# EAA690_RFID_Door.net
KiCad netlist of a schematic drawn in EAGLE
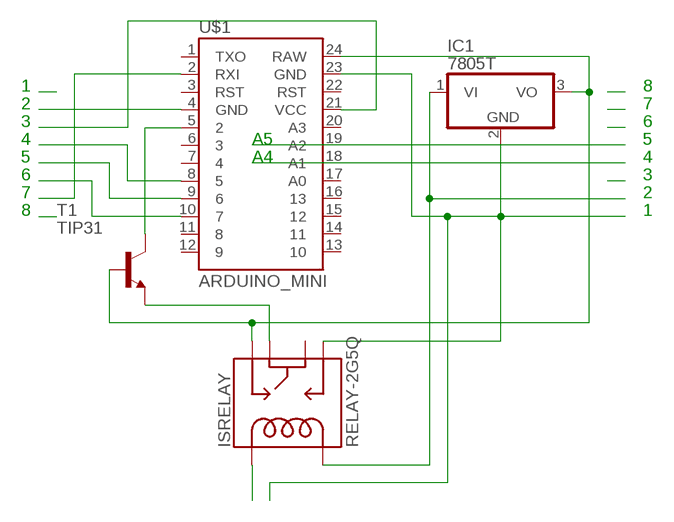
[diagram p0: schematic, sheet 1]

(export (version "E")
  (design (tool "Eeschema 10.0.6"))
  (components
    (comp (ref "IC1")
      (value "7805T")
      (footprint "eagle-import:TO220H")
      (libsource (lib "eagle-import") (part "78T05"))
    )
    (comp (ref "ISRELAY")
      (value "RELAY-2G5Q")
      (footprint "eagle-import:RELAY-G5V")
      (libsource (lib "eagle-import") (part "RELAY-2G5Q"))
    )
    (comp (ref "T1")
      (value "TIP31")
      (footprint "eagle-import:TO220")
      (libsource (lib "eagle-import") (part "TIP31"))
    )
    (comp (ref "U$1")
      (value "ARDUINO_MINI")
      (footprint "eagle-import:ARDUINO_MINI")
      (libsource (lib "eagle-import") (part "ARDUINO_MINI"))
    )
  )
  (nets
    (net (code "1") (name "Net-(IC1-GND)") (class "Default")
      (node (ref "IC1") (pin "2") (pinfunction "GND_2") (pintype "passive"))
      (node (ref "ISRELAY") (pin "10") (pinfunction "10_10") (pintype "bidirectional"))
      (node (ref "U$1") (pin "23") (pinfunction "GND_23") (pintype "bidirectional"))
    )
    (net (code "2") (name "Net-(IC1-VI)") (class "Default")
      (node (ref "IC1") (pin "1") (pinfunction "VI_1") (pintype "input"))
      (node (ref "ISRELAY") (pin "9") (pinfunction "9_9") (pintype "bidirectional"))
    )
    (net (code "3") (name "Net-(IC1-VO)") (class "Default")
      (node (ref "IC1") (pin "3") (pinfunction "VO_3") (pintype "passive"))
      (node (ref "ISRELAY") (pin "1") (pinfunction "1_1") (pintype "bidirectional"))
      (node (ref "T1") (pin "1") (pinfunction "B_1") (pintype "passive"))
      (node (ref "U$1") (pin "24") (pinfunction "RAW_24") (pintype "bidirectional"))
    )
    (net (code "4") (name "Net-(T1-C)") (class "Default")
      (node (ref "T1") (pin "2") (pinfunction "C_2") (pintype "passive"))
      (node (ref "U$1") (pin "5") (pinfunction "2_5") (pintype "bidirectional"))
    )
    (net (code "5") (name "Net-(T1-E)") (class "Default")
      (node (ref "ISRELAY") (pin "5") (pinfunction "5_5") (pintype "bidirectional"))
      (node (ref "T1") (pin "3") (pinfunction "E_3") (pintype "passive"))
    )
    (net (code "6") (name "unconnected-(ISRELAY-Pad2)") (class "Default")
      (node (ref "ISRELAY") (pin "2") (pinfunction "2_2") (pintype "bidirectional"))
    )
    (net (code "7") (name "unconnected-(ISRELAY-Pad6)") (class "Default")
      (node (ref "ISRELAY") (pin "6") (pinfunction "6_6") (pintype "bidirectional"))
    )
    (net (code "8") (name "unconnected-(U$1-3-Pad6)") (class "Default")
      (node (ref "U$1") (pin "6") (pinfunction "3_6") (pintype "bidirectional"))
    )
    (net (code "9") (name "unconnected-(U$1-4-Pad7)") (class "Default")
      (node (ref "U$1") (pin "7") (pinfunction "4_7") (pintype "bidirectional"))
    )
    (net (code "10") (name "unconnected-(U$1-5-Pad8)") (class "Default")
      (node (ref "U$1") (pin "8") (pinfunction "5_8") (pintype "bidirectional"))
    )
    (net (code "11") (name "unconnected-(U$1-6-Pad9)") (class "Default")
      (node (ref "U$1") (pin "9") (pinfunction "6_9") (pintype "bidirectional"))
    )
    (net (code "12") (name "unconnected-(U$1-7-Pad10)") (class "Default")
      (node (ref "U$1") (pin "10") (pinfunction "7_10") (pintype "bidirectional"))
    )
    (net (code "13") (name "unconnected-(U$1-8-Pad11)") (class "Default")
      (node (ref "U$1") (pin "11") (pinfunction "8_11") (pintype "bidirectional"))
    )
    (net (code "14") (name "unconnected-(U$1-9-Pad12)") (class "Default")
      (node (ref "U$1") (pin "12") (pinfunction "9_12") (pintype "bidirectional"))
    )
    (net (code "15") (name "unconnected-(U$1-10-Pad13)") (class "Default")
      (node (ref "U$1") (pin "13") (pinfunction "10_13") (pintype "bidirectional"))
    )
    (net (code "16") (name "unconnected-(U$1-11-Pad14)") (class "Default")
      (node (ref "U$1") (pin "14") (pinfunction "11_14") (pintype "bidirectional"))
    )
    (net (code "17") (name "unconnected-(U$1-12-Pad15)") (class "Default")
      (node (ref "U$1") (pin "15") (pinfunction "12_15") (pintype "bidirectional"))
    )
    (net (code "18") (name "unconnected-(U$1-13-Pad16)") (class "Default")
      (node (ref "U$1") (pin "16") (pinfunction "13_16") (pintype "bidirectional"))
    )
    (net (code "19") (name "unconnected-(U$1-A0-Pad17)") (class "Default")
      (node (ref "U$1") (pin "17") (pinfunction "A0_17") (pintype "bidirectional"))
    )
    (net (code "20") (name "unconnected-(U$1-A1-Pad18)") (class "Default")
      (node (ref "U$1") (pin "18") (pinfunction "A1_18") (pintype "bidirectional"))
    )
    (net (code "21") (name "unconnected-(U$1-A2-Pad19)") (class "Default")
      (node (ref "U$1") (pin "19") (pinfunction "A2_19") (pintype "bidirectional"))
    )
    (net (code "22") (name "unconnected-(U$1-A3-Pad20)") (class "Default")
      (node (ref "U$1") (pin "20") (pinfunction "A3_20") (pintype "bidirectional"))
    )
    (net (code "23") (name "unconnected-(U$1-GND-Pad4)") (class "Default")
      (node (ref "U$1") (pin "4") (pinfunction "GND_4") (pintype "bidirectional"))
    )
    (net (code "24") (name "unconnected-(U$1-RST-Pad3)") (class "Default")
      (node (ref "U$1") (pin "3") (pinfunction "RST_3") (pintype "bidirectional"))
    )
    (net (code "25") (name "unconnected-(U$1-RST-Pad22)") (class "Default")
      (node (ref "U$1") (pin "22") (pinfunction "RST_22") (pintype "bidirectional"))
    )
    (net (code "26") (name "unconnected-(U$1-RXI-Pad2)") (class "Default")
      (node (ref "U$1") (pin "2") (pinfunction "RXI_2") (pintype "bidirectional"))
    )
    (net (code "27") (name "unconnected-(U$1-TXO-Pad1)") (class "Default")
      (node (ref "U$1") (pin "1") (pinfunction "TXO_1") (pintype "bidirectional"))
    )
    (net (code "28") (name "unconnected-(U$1-VCC-Pad21)") (class "Default")
      (node (ref "U$1") (pin "21") (pinfunction "VCC_21") (pintype "bidirectional"))
    )
  )
)
